# Supply_12V_ISOL.net
KiCad netlist of a schematic drawn in Altium Designer
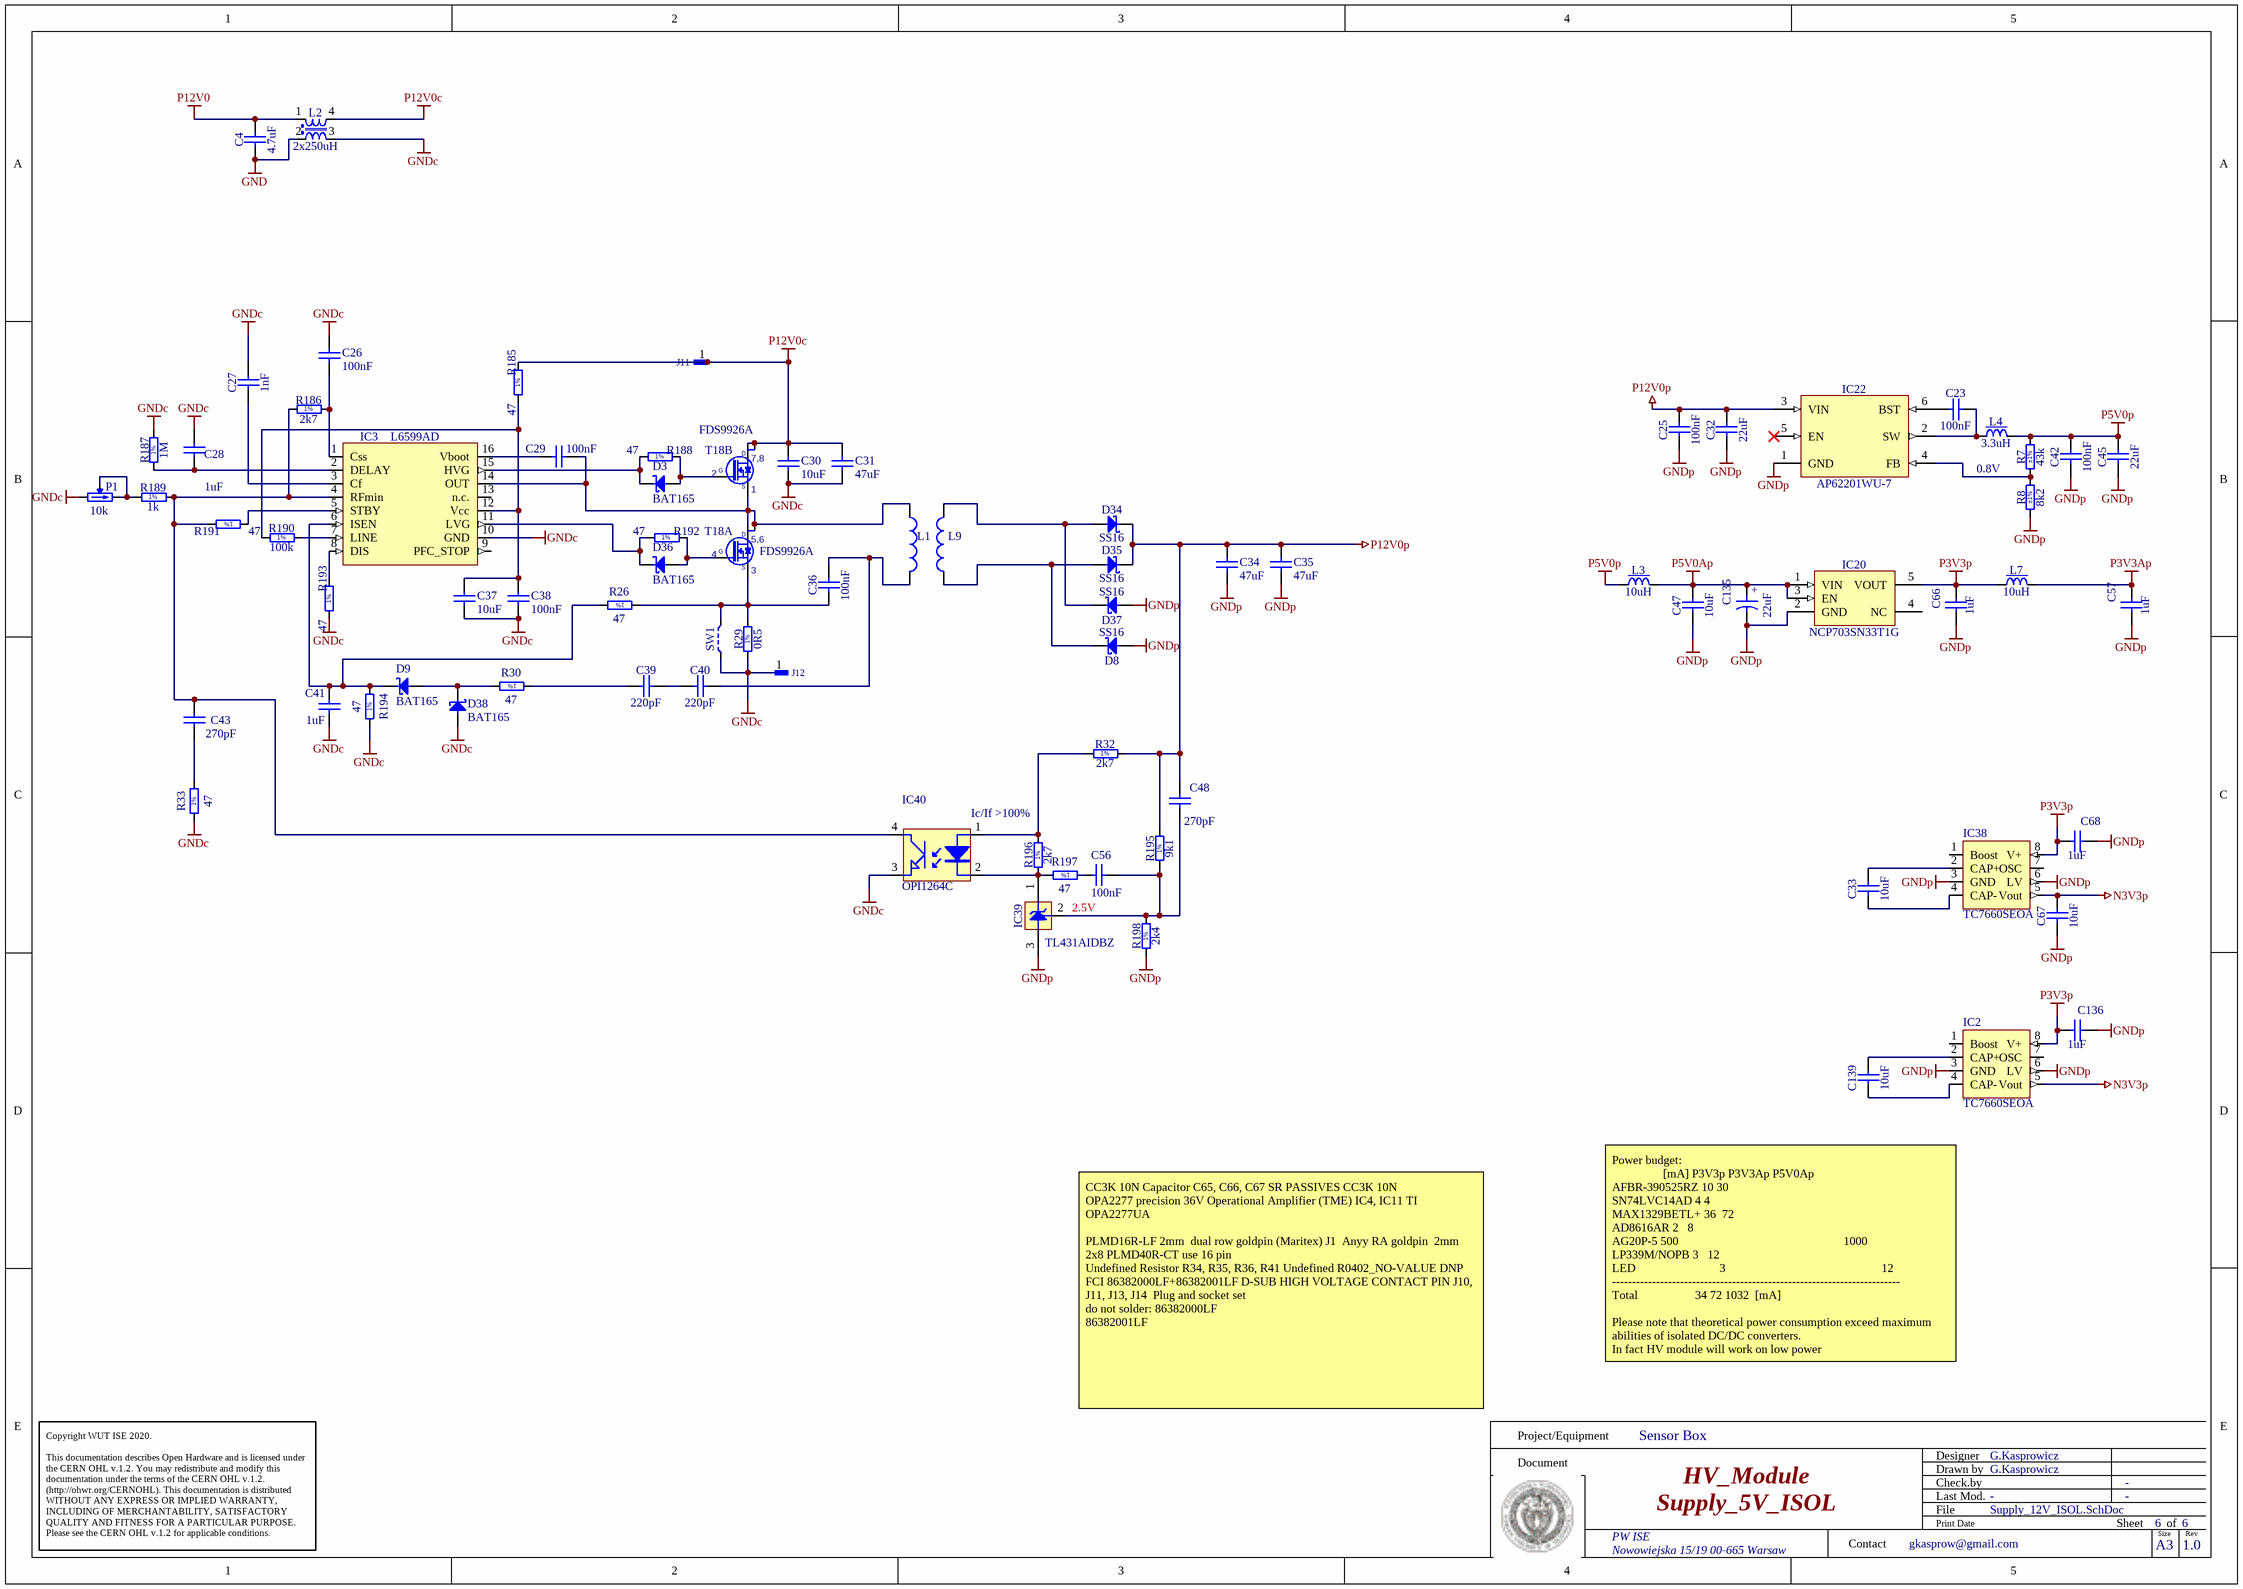
[diagram p0: Supply_12V_ISOL.SchDoc]

(export (version "E")
  (design (tool "Eeschema 10.0.6"))
  (components
    (comp (ref "C4")
      (value "4.7uF")
      (footprint "CAPC2012X145N")
      (description "Non-polarised capacitor")
      (fields
        (field (name "PART NUMBER") "CC0805_4.7UF_50V_10%_X7R")
        (field (name "VOLTAGE") "50V")
        (field (name "AUTHOR") "CERN DEM JMW")
      )
      (libsource (lib "Capacitors") (part "Capacitor - non polarized"))
    )
    (comp (ref "C23")
      (value "100nF")
      (footprint "CAPC1005X55N")
      (description "Non-polarised capacitor")
      (fields
        (field (name "PART NUMBER") "CC0402_100NF_16V_10%_X5R")
        (field (name "VOLTAGE") "16V")
        (field (name "AUTHOR") "CERN DEM JLC")
      )
      (libsource (lib "Capacitors") (part "Capacitor - non polarized"))
    )
    (comp (ref "C25")
      (value "100nF")
      (footprint "CAPC1005X55N")
      (description "Non-polarised capacitor")
      (fields
        (field (name "PART NUMBER") "CC0402_100NF_16V_10%_X5R")
        (field (name "VOLTAGE") "16V")
        (field (name "AUTHOR") "CERN DEM JLC")
      )
      (libsource (lib "Capacitors") (part "Capacitor - non polarized"))
    )
    (comp (ref "C26")
      (value "100nF")
      (footprint "CAPC1005X55N")
      (description "Non-polarised capacitor")
      (fields
        (field (name "PART NUMBER") "CC0402_100NF_16V_10%_X7R")
        (field (name "VOLTAGE") "16V")
        (field (name "AUTHOR") "CERN DEM JLC")
      )
      (libsource (lib "Capacitors") (part "Capacitor - non polarized"))
    )
    (comp (ref "C27")
      (value "1nF")
      (footprint "CAPC1608X90N")
      (description "Non-polarised capacitor")
      (fields
        (field (name "PART NUMBER") "CC0603_1NF_50V_5%_NP0")
        (field (name "VOLTAGE") "50V")
        (field (name "AUTHOR") "CERN DEM JLC")
      )
      (libsource (lib "Capacitors") (part "Capacitor - non polarized"))
    )
    (comp (ref "C28")
      (value "1uF")
      (footprint "CAPC1608X87N")
      (description "Non-polarised capacitor")
      (fields
        (field (name "PART NUMBER") "CC0603_1UF_25V_10%_X7R")
        (field (name "VOLTAGE") "25V")
        (field (name "AUTHOR") "CERN DEM JLC")
      )
      (libsource (lib "Capacitors") (part "Capacitor - non polarized"))
    )
    (comp (ref "C29")
      (value "100nF")
      (footprint "CAPC1005X55N")
      (description "Non-polarised capacitor")
      (fields
        (field (name "PART NUMBER") "CC0402_100NF_16V_10%_X7R")
        (field (name "VOLTAGE") "16V")
        (field (name "AUTHOR") "CERN DEM JLC")
      )
      (libsource (lib "Capacitors") (part "Capacitor - non polarized"))
    )
    (comp (ref "C30")
      (value "10uF")
      (footprint "CAPC3216X180N")
      (description "Non-polarised capacitor")
      (fields
        (field (name "PART NUMBER") "CC1206_10UF_25V_10%_X7R")
        (field (name "VOLTAGE") "25V")
        (field (name "AUTHOR") "CERN DEM JLC")
      )
      (libsource (lib "Capacitors") (part "Capacitor - non polarized"))
    )
    (comp (ref "C31")
      (value "47uF")
      (footprint "CAPC3216X180N")
      (description "Non-polarised capacitor")
      (fields
        (field (name "PART NUMBER") "CC1206_47UF_25V_20%_X5R")
        (field (name "VOLTAGE") "25V")
        (field (name "AUTHOR") "CERN DEM JLC")
      )
      (libsource (lib "Capacitors") (part "Capacitor - non polarized"))
    )
    (comp (ref "C32")
      (value "22uF")
      (footprint "CAPC2012X135N")
      (description "Non-polarised capacitor")
      (fields
        (field (name "PART NUMBER") "CC0805_22UF_16V_10%_X5R")
        (field (name "VOLTAGE") "16V")
        (field (name "AUTHOR") "CERN DEM JLC")
      )
      (libsource (lib "Capacitors") (part "Capacitor - non polarized"))
    )
    (comp (ref "C33")
      (value "10uF")
      (footprint "CAPC1608X80N")
      (description "Non-polarised capacitor")
      (fields
        (field (name "PART NUMBER") "CC0603_10UF_16V_20%_X5R")
        (field (name "VOLTAGE") "16V")
        (field (name "AUTHOR") "CERN DEM MR")
      )
      (libsource (lib "Capacitors") (part "Capacitor - non polarized"))
    )
    (comp (ref "C34")
      (value "47uF")
      (footprint "CAPC3216X180N")
      (description "Non-polarised capacitor")
      (fields
        (field (name "PART NUMBER") "CC1206_47UF_25V_20%_X5R")
        (field (name "VOLTAGE") "25V")
        (field (name "AUTHOR") "CERN DEM JLC")
      )
      (libsource (lib "Capacitors") (part "Capacitor - non polarized"))
    )
    (comp (ref "C35")
      (value "47uF")
      (footprint "CAPC3216X180N")
      (description "Non-polarised capacitor")
      (fields
        (field (name "PART NUMBER") "CC1206_47UF_25V_20%_X5R")
        (field (name "VOLTAGE") "25V")
        (field (name "AUTHOR") "CERN DEM JLC")
      )
      (libsource (lib "Capacitors") (part "Capacitor - non polarized"))
    )
    (comp (ref "C36")
      (value "100nF")
      (footprint "CAPC4532X250N")
      (description "Non-polarised capacitor")
      (fields
        (field (name "PART NUMBER") "CC1812_100NF_500V_10%_X7R")
        (field (name "VOLTAGE") "500V")
        (field (name "AUTHOR") "CERN DEM JMW")
      )
      (libsource (lib "Capacitors") (part "Capacitor - non polarized"))
    )
    (comp (ref "C37")
      (value "10uF")
      (footprint "CAPC3216X180N")
      (description "Non-polarised capacitor")
      (fields
        (field (name "PART NUMBER") "CC1206_10UF_25V_10%_X7R")
        (field (name "VOLTAGE") "25V")
        (field (name "AUTHOR") "CERN DEM JLC")
      )
      (libsource (lib "Capacitors") (part "Capacitor - non polarized"))
    )
    (comp (ref "C38")
      (value "100nF")
      (footprint "CAPC1005X55N")
      (description "Non-polarised capacitor")
      (fields
        (field (name "PART NUMBER") "CC0402_100NF_16V_10%_X7R")
        (field (name "VOLTAGE") "16V")
        (field (name "AUTHOR") "CERN DEM JLC")
      )
      (libsource (lib "Capacitors") (part "Capacitor - non polarized"))
    )
    (comp (ref "C39")
      (value "220pF")
      (footprint "CAPC3225X200N")
      (description "Non-polarised capacitor")
      (fields
        (field (name "PART NUMBER") "CMIC1210_220PF_100V_0.5PF_CORNELL_MC12FA221D-F")
        (field (name "VOLTAGE") "100V")
        (field (name "AUTHOR") "CERN DEM JLC")
      )
      (libsource (lib "Capacitors") (part "Capacitor - non polarized"))
    )
    (comp (ref "C40")
      (value "220pF")
      (footprint "CAPC3225X200N")
      (description "Non-polarised capacitor")
      (fields
        (field (name "PART NUMBER") "CMIC1210_220PF_100V_0.5PF_CORNELL_MC12FA221D-F")
        (field (name "VOLTAGE") "100V")
        (field (name "AUTHOR") "CERN DEM JLC")
      )
      (libsource (lib "Capacitors") (part "Capacitor - non polarized"))
    )
    (comp (ref "C41")
      (value "1uF")
      (footprint "CAPC1608X87N")
      (description "Non-polarised capacitor")
      (fields
        (field (name "PART NUMBER") "CC0603_1UF_25V_10%_X7R")
        (field (name "VOLTAGE") "25V")
        (field (name "AUTHOR") "CERN DEM JLC")
      )
      (libsource (lib "Capacitors") (part "Capacitor - non polarized"))
    )
    (comp (ref "C42")
      (value "100nF")
      (footprint "CAPC1005X55N")
      (description "Non-polarised capacitor")
      (fields
        (field (name "PART NUMBER") "CC0402_100NF_16V_10%_X5R")
        (field (name "VOLTAGE") "16V")
        (field (name "AUTHOR") "CERN DEM JLC")
      )
      (libsource (lib "Capacitors") (part "Capacitor - non polarized"))
    )
    (comp (ref "C43")
      (value "270pF")
      (footprint "CAPC1608X87N")
      (description "Non-polarised capacitor")
      (fields
        (field (name "PART NUMBER") "CC0603_270PF_50V_5%_NP0")
        (field (name "VOLTAGE") "50V")
        (field (name "AUTHOR") "CERN DEM JLC")
      )
      (libsource (lib "Capacitors") (part "Capacitor - non polarized"))
    )
    (comp (ref "C45")
      (value "22uF")
      (footprint "CAPC2012X135N")
      (description "Non-polarised capacitor")
      (fields
        (field (name "PART NUMBER") "CC0805_22UF_16V_10%_X5R")
        (field (name "VOLTAGE") "16V")
        (field (name "AUTHOR") "CERN DEM JLC")
      )
      (libsource (lib "Capacitors") (part "Capacitor - non polarized"))
    )
    (comp (ref "C47")
      (value "10uF")
      (footprint "CAPC1608X80N")
      (description "Non-polarised capacitor")
      (fields
        (field (name "PART NUMBER") "CC0603_10UF_16V_20%_X5R")
        (field (name "VOLTAGE") "16V")
        (field (name "AUTHOR") "CERN DEM MR")
      )
      (libsource (lib "Capacitors") (part "Capacitor - non polarized"))
    )
    (comp (ref "C48")
      (value "270pF")
      (footprint "CAPC1608X87N")
      (description "Non-polarised capacitor")
      (fields
        (field (name "PART NUMBER") "CC0603_270PF_50V_5%_NP0")
        (field (name "VOLTAGE") "50V")
        (field (name "AUTHOR") "CERN DEM JLC")
      )
      (libsource (lib "Capacitors") (part "Capacitor - non polarized"))
    )
    (comp (ref "C56")
      (value "100nF")
      (footprint "CAPC1005X55N")
      (description "Non-polarised capacitor")
      (fields
        (field (name "PART NUMBER") "CC0402_100NF_16V_10%_X7R")
        (field (name "VOLTAGE") "16V")
        (field (name "AUTHOR") "CERN DEM JLC")
      )
      (libsource (lib "Capacitors") (part "Capacitor - non polarized"))
    )
    (comp (ref "C57")
      (value "1uF")
      (footprint "CAPC1005X55N")
      (description "Non-polarised capacitor")
      (fields
        (field (name "PART NUMBER") "CC0402_1UF_16V_10%_X5R")
        (field (name "VOLTAGE") "16V")
        (field (name "AUTHOR") "CERN DEM JLC")
      )
      (libsource (lib "Capacitors") (part "Capacitor - non polarized"))
    )
    (comp (ref "C66")
      (value "1uF")
      (footprint "CAPC1005X55N")
      (description "Non-polarised capacitor")
      (fields
        (field (name "PART NUMBER") "CC0402_1UF_16V_10%_X5R")
        (field (name "VOLTAGE") "16V")
        (field (name "AUTHOR") "CERN DEM JLC")
      )
      (libsource (lib "Capacitors") (part "Capacitor - non polarized"))
    )
    (comp (ref "C67")
      (value "10uF")
      (footprint "CAPC1608X80N")
      (description "Non-polarised capacitor")
      (fields
        (field (name "PART NUMBER") "CC0603_10UF_16V_20%_X5R")
        (field (name "VOLTAGE") "16V")
        (field (name "AUTHOR") "CERN DEM MR")
      )
      (libsource (lib "Capacitors") (part "Capacitor - non polarized"))
    )
    (comp (ref "C68")
      (value "1uF")
      (footprint "CAPC1005X55N")
      (description "Non-polarised capacitor")
      (fields
        (field (name "PART NUMBER") "CC0402_1UF_16V_10%_X5R")
        (field (name "VOLTAGE") "16V")
        (field (name "AUTHOR") "CERN DEM JLC")
      )
      (libsource (lib "Capacitors") (part "Capacitor - non polarized"))
    )
    (comp (ref "C135")
      (value "22uF")
      (footprint "CAPMP3528X210N")
      (description "Polarised capacitor")
      (fields
        (field (name "PART NUMBER") "CTE3528-21_22UF_20V_10%")
        (field (name "VOLTAGE") "20V")
        (field (name "AUTHOR") "CERN DEM JLC")
      )
      (libsource (lib "Capacitors") (part "Capacitor - polarized"))
    )
    (comp (ref "C136")
      (value "1uF")
      (footprint "CAPC1005X55N")
      (description "Non-polarised capacitor")
      (fields
        (field (name "PART NUMBER") "CC0402_1UF_16V_10%_X5R")
        (field (name "VOLTAGE") "16V")
        (field (name "AUTHOR") "CERN DEM JLC")
      )
      (libsource (lib "Capacitors") (part "Capacitor - non polarized"))
    )
    (comp (ref "C139")
      (value "10uF")
      (footprint "CAPC1608X80N")
      (description "Non-polarised capacitor")
      (fields
        (field (name "PART NUMBER") "CC0603_10UF_16V_20%_X5R")
        (field (name "VOLTAGE") "16V")
        (field (name "AUTHOR") "CERN DEM MR")
      )
      (libsource (lib "Capacitors") (part "Capacitor - non polarized"))
    )
    (comp (ref "D3")
      (value "BAT165")
      (footprint "SOD2512X110N")
      (description "Schottky Diode")
      (fields
        (field (name "VOLTAGE") "40V")
        (field (name "POWER") "750mA")
        (field (name "AUTHOR") "CERN DEM JLC")
      )
      (libsource (lib "ICs And Semiconductors") (part "Diode Schottky"))
    )
    (comp (ref "D8")
      (value "SS16")
      (footprint "DIOM5127X229N")
      (description "Schottky Diode")
      (fields
        (field (name "VOLTAGE") "60V")
        (field (name "POWER") "1A")
        (field (name "AUTHOR") "CERN DEM JLC")
      )
      (libsource (lib "ICs And Semiconductors") (part "Diode Schottky"))
    )
    (comp (ref "D9")
      (value "BAT165")
      (footprint "SOD2512X110N")
      (description "Schottky Diode")
      (fields
        (field (name "VOLTAGE") "40V")
        (field (name "POWER") "750mA")
        (field (name "AUTHOR") "CERN DEM JLC")
      )
      (libsource (lib "ICs And Semiconductors") (part "Diode Schottky"))
    )
    (comp (ref "D34")
      (value "SS16")
      (footprint "DIOM5127X229N")
      (description "Schottky Diode")
      (fields
        (field (name "VOLTAGE") "60V")
        (field (name "POWER") "1A")
        (field (name "AUTHOR") "CERN DEM JLC")
      )
      (libsource (lib "ICs And Semiconductors") (part "Diode Schottky"))
    )
    (comp (ref "D35")
      (value "SS16")
      (footprint "DIOM5127X229N")
      (description "Schottky Diode")
      (fields
        (field (name "VOLTAGE") "60V")
        (field (name "POWER") "1A")
        (field (name "AUTHOR") "CERN DEM JLC")
      )
      (libsource (lib "ICs And Semiconductors") (part "Diode Schottky"))
    )
    (comp (ref "D36")
      (value "BAT165")
      (footprint "SOD2512X110N")
      (description "Schottky Diode")
      (fields
        (field (name "VOLTAGE") "40V")
        (field (name "POWER") "750mA")
        (field (name "AUTHOR") "CERN DEM JLC")
      )
      (libsource (lib "ICs And Semiconductors") (part "Diode Schottky"))
    )
    (comp (ref "D37")
      (value "SS16")
      (footprint "DIOM5127X229N")
      (description "Schottky Diode")
      (fields
        (field (name "VOLTAGE") "60V")
        (field (name "POWER") "1A")
        (field (name "AUTHOR") "CERN DEM JLC")
      )
      (libsource (lib "ICs And Semiconductors") (part "Diode Schottky"))
    )
    (comp (ref "D38")
      (value "BAT165")
      (footprint "SOD2512X110N")
      (description "Schottky Diode")
      (fields
        (field (name "VOLTAGE") "40V")
        (field (name "POWER") "750mA")
        (field (name "AUTHOR") "CERN DEM JLC")
      )
      (libsource (lib "ICs And Semiconductors") (part "Diode Schottky"))
    )
    (comp (ref "IC2")
      (value "TC7660SEOA")
      (footprint "SO-8")
      (description "20mA PUMP DC-TO-DC VOLTAGE CONVERTER")
      (libsource (lib "LIBRARY_SCH") (part "PM_TC7660"))
    )
    (comp (ref "IC3")
      (value "L6599AD")
      (footprint "SOIC127P600X175-16N")
      (description "Improved high voltage resonant LLC controller")
      (fields (field (name "MANUFACTURER") "ST MICROELECTRONICS") (field (name "AUTHOR") "GK"))
      (libsource (lib "LIBRARY_SCH") (part "PM_L6599"))
    )
    (comp (ref "IC20")
      (value "NCP703SN33T1G")
      (footprint "SOT95P275X110-5N")
      (description "3.3V 300mA, Ultra-Low Quiescent Current, IQ 12uA, Ultra-Low Noise, LDO Voltage Regulator")
      (fields (field (name "MANUFACTURER") "ON SEMICONDUCTOR") (field (name "AUTHOR") "CERN DEM JLC"))
      (libsource (lib "ICs And Semiconductors") (part "NCP703SN"))
    )
    (comp (ref "IC22")
      (value "AP62201WU-7")
      (footprint "SOT95P280X100-6N")
      (description "4.2V TO 18V INPUT, 2A LOW IQ SYNCHRONOUS BUCK CONVERTER")
      (fields (field (name "MANUFACTURER") "DIODES INCORPORATED") (field (name "AUTHOR") "CERN DEM HF"))
      (libsource (lib "ICs And Semiconductors") (part "AP62201WU"))
    )
    (comp (ref "IC38")
      (value "TC7660SEOA")
      (footprint "SO-8")
      (description "20mA PUMP DC-TO-DC VOLTAGE CONVERTER")
      (libsource (lib "LIBRARY_SCH") (part "PM_TC7660"))
    )
    (comp (ref "IC39")
      (value "TL431AIDBZ")
      (footprint "SOT95P237X112-3N")
      (description "Precision Reference 1=Cathode 2=Adj 3=Anode")
      (fields (field (name "MANUFACTURER") "TEXAS INSTRUMENTS") (field (name "AUTHOR") "CERN DEM JMW"))
      (libsource (lib "ICs And Semiconductors") (part "VREF 1C-2ADJ-3A"))
    )
    (comp (ref "IC40")
      (value "OPI1264C")
      (footprint "OPI1264C")
      (description "10kV opto-coupler")
      (libsource (lib "LIBRARY_SCH") (part "OPTO-OPI1264C"))
    )
    (comp (ref "J11")
      (value "SMD Pad")
      (footprint "R400X300")
      (description "Single SMD Pad")
      (fields (field (name "PART NUMBER") "SMD_PAD_4X3MM") (field (name "AUTHOR") "CERN DEM JLC"))
      (libsource (lib "Eletro-mechanical") (part "Single SMD Pad"))
    )
    (comp (ref "J12")
      (value "SMD Pad")
      (footprint "R400X300")
      (description "Single SMD Pad")
      (fields (field (name "PART NUMBER") "SMD_PAD_4X3MM") (field (name "AUTHOR") "CERN DEM JLC"))
      (libsource (lib "") (part "Single SMD Pad_1"))
    )
    (comp (ref "L1")
      (value "6.8uH")
      (footprint "760308101104")
      (description "WE-WPCC Wireless Power Transfer Transmitter Coil, THT, works with Qi Tx IC's, 6.8uH, 50W")
      (fields
        (field (name "MANUFACTURER PART NUMBER") "760308101104")
        (field (name "MANUFACTURER") "Wurth Elektronik")
      )
      (libsource (lib "Altium_WE-WPCC (rev23b)") (part "760308101104"))
    )
    (comp (ref "L2")
      (value "2x250uH")
      (footprint "IND_WURTH_WE-SL2")
      (description "Inductor Common Mode")
      (fields
        (field (name "PART NUMBER") "IND_250UH_50%_WURTH_WE-SL2-744224")
        (field (name "POWER") "1.2A")
        (field (name "AUTHOR") "CERN DEM JLC")
      )
      (libsource (lib "Inductors & Transformers") (part "Inductor Common Mode 1Dot-4 2Dot-3"))
    )
    (comp (ref "L3")
      (value "10uH")
      (footprint "IND_BOURNS_PM43")
      (description "Inductor With Core")
      (fields
        (field (name "PART NUMBER") "IND_10UH_20%_BOURNS_PM43")
        (field (name "POWER") "1.15A")
        (field (name "AUTHOR") "CERN DEM JLC")
      )
      (libsource (lib "Inductors & Transformers") (part "Inductor With Magnetic core"))
    )
    (comp (ref "L4")
      (value "3.3uH")
      (footprint "IND_WURTH_WE-TPC_4828")
      (description "Inductor With Core")
      (fields
        (field (name "PART NUMBER") "IND_3.3UH_30%_WURTH_WE-TPC_744043003")
        (field (name "POWER") "2.15A")
        (field (name "AUTHOR") "CERN DEM JLC")
      )
      (libsource (lib "Inductors & Transformers") (part "Inductor With Magnetic core"))
    )
    (comp (ref "L7")
      (value "10uH")
      (footprint "IND_BOURNS_PM43")
      (description "Inductor With Core")
      (fields
        (field (name "PART NUMBER") "IND_10UH_20%_BOURNS_PM43")
        (field (name "POWER") "1.15A")
        (field (name "AUTHOR") "CERN DEM JLC")
      )
      (libsource (lib "Inductors & Transformers") (part "Inductor With Magnetic core"))
    )
    (comp (ref "L9")
      (value "6.8uH")
      (footprint "760308101104")
      (description "WE-WPCC Wireless Power Transfer Transmitter Coil, THT, works with Qi Tx IC's, 6.8uH, 50W")
      (fields
        (field (name "MANUFACTURER PART NUMBER") "760308101104")
        (field (name "MANUFACTURER") "Wurth Elektronik")
      )
      (libsource (lib "Altium_WE-WPCC (rev23b)") (part "760308101104"))
    )
    (comp (ref "P1")
      (value "10k")
      (footprint "TRIM_BOURNS_3314G-1")
      (description "Trimming Potentiometer")
      (fields
        (field (name "PART NUMBER") "TRIM_1T_10K_BOURNS_3314G-1-103E")
        (field (name "POWER") "0.25W")
        (field (name "AUTHOR") "CERN DEM JLC")
      )
      (libsource (lib "Resistors") (part "Trimming Potentiometer"))
    )
    (comp (ref "R7")
      (value "43k")
      (footprint "RESC1005X40N")
      (description "Resistor - 1%")
      (fields
        (field (name "TOLERANCE") "±1%")
        (field (name "PART NUMBER") "R0402_43K_1%_0.0625W_100PPM")
        (field (name "POWER") "0.0625W")
        (field (name "AUTHOR") "CERN DEM JLC")
      )
      (libsource (lib "") (part "Resistor - 1%_1"))
    )
    (comp (ref "R8")
      (value "8k2")
      (footprint "RESC1005X40N")
      (description "Resistor - 1%")
      (fields
        (field (name "TOLERANCE") "±1%")
        (field (name "PART NUMBER") "R0402_8K2_1%_0.0625W_100PPM")
        (field (name "POWER") "0.0625W")
        (field (name "AUTHOR") "CERN DEM JLC")
      )
      (libsource (lib "") (part "Resistor - 1%_1"))
    )
    (comp (ref "R26")
      (value "47")
      (footprint "RESC1608X55N")
      (description "Resistor - 1%")
      (fields
        (field (name "PART NUMBER") "R0603_47R_1%_0.1W_100PPM")
        (field (name "POWER") "0.1W")
        (field (name "AUTHOR") "CERN DEM JLC")
      )
      (libsource (lib "Resistors") (part "Resistor - 1%"))
    )
    (comp (ref "R29")
      (value "0R5")
      (footprint "RESC6532X80N")
      (description "Resistor - 1%")
      (fields
        (field (name "PART NUMBER") "R2512_0R5_1%_1.5W_100PPM")
        (field (name "POWER") "1.5W")
        (field (name "AUTHOR") "CERN DEM JLC")
      )
      (libsource (lib "Resistors") (part "Resistor - 1%"))
    )
    (comp (ref "R30")
      (value "47")
      (footprint "RESC1608X55N")
      (description "Resistor - 1%")
      (fields
        (field (name "PART NUMBER") "R0603_47R_1%_0.1W_100PPM")
        (field (name "POWER") "0.1W")
        (field (name "AUTHOR") "CERN DEM JLC")
      )
      (libsource (lib "Resistors") (part "Resistor - 1%"))
    )
    (comp (ref "R32")
      (value "2k7")
      (footprint "RESC1608X55N")
      (description "Resistor - 1%")
      (fields
        (field (name "PART NUMBER") "R0603_2K7_1%_0.1W_100PPM")
        (field (name "POWER") "0.1W")
        (field (name "AUTHOR") "CERN DEM JLC")
      )
      (libsource (lib "Resistors") (part "Resistor - 1%"))
    )
    (comp (ref "R33")
      (value "47")
      (footprint "RESC1608X55N")
      (description "Resistor - 1%")
      (fields
        (field (name "PART NUMBER") "R0603_47R_1%_0.1W_100PPM")
        (field (name "POWER") "0.1W")
        (field (name "AUTHOR") "CERN DEM JLC")
      )
      (libsource (lib "Resistors") (part "Resistor - 1%"))
    )
    (comp (ref "R185")
      (value "47")
      (footprint "RESC1608X55N")
      (description "Resistor - 1%")
      (fields
        (field (name "PART NUMBER") "R0603_47R_1%_0.1W_100PPM")
        (field (name "POWER") "0.1W")
        (field (name "AUTHOR") "CERN DEM JLC")
      )
      (libsource (lib "Resistors") (part "Resistor - 1%"))
    )
    (comp (ref "R186")
      (value "2k7")
      (footprint "RESC1608X55N")
      (description "Resistor - 1%")
      (fields
        (field (name "PART NUMBER") "R0603_2K7_1%_0.1W_100PPM")
        (field (name "POWER") "0.1W")
        (field (name "AUTHOR") "CERN DEM JLC")
      )
      (libsource (lib "Resistors") (part "Resistor - 1%"))
    )
    (comp (ref "R187")
      (value "1M")
      (footprint "RESC1608X55N")
      (description "Resistor - 1%")
      (fields
        (field (name "PART NUMBER") "R0603_1M_1%_0.1W_100PPM")
        (field (name "POWER") "0.1W")
        (field (name "AUTHOR") "CERN DEM JLC")
      )
      (libsource (lib "Resistors") (part "Resistor - 1%"))
    )
    (comp (ref "R188")
      (value "47")
      (footprint "RESC1608X55N")
      (description "Resistor - 1%")
      (fields
        (field (name "PART NUMBER") "R0603_47R_1%_0.1W_100PPM")
        (field (name "POWER") "0.1W")
        (field (name "AUTHOR") "CERN DEM JLC")
      )
      (libsource (lib "Resistors") (part "Resistor - 1%"))
    )
    (comp (ref "R189")
      (value "1k")
      (footprint "RESC1005X40N")
      (description "Resistor - 1%")
      (fields
        (field (name "PART NUMBER") "R0402_1K_1%_0.0625W_100PPM")
        (field (name "POWER") "0.0625W")
        (field (name "AUTHOR") "CERN DEM JLC")
      )
      (libsource (lib "Resistors") (part "Resistor - 1%"))
    )
    (comp (ref "R190")
      (value "100k")
      (footprint "RESC1005X40N")
      (description "Resistor - 1%")
      (fields
        (field (name "PART NUMBER") "R0402_100K_1%_0.0625W_100PPM")
        (field (name "POWER") "0.0625W")
        (field (name "AUTHOR") "CERN DEM JLC")
      )
      (libsource (lib "Resistors") (part "Resistor - 1%"))
    )
    (comp (ref "R191")
      (value "47")
      (footprint "RESC1608X55N")
      (description "Resistor - 1%")
      (fields
        (field (name "PART NUMBER") "R0603_47R_1%_0.1W_100PPM")
        (field (name "POWER") "0.1W")
        (field (name "AUTHOR") "CERN DEM JLC")
      )
      (libsource (lib "Resistors") (part "Resistor - 1%"))
    )
    (comp (ref "R192")
      (value "47")
      (footprint "RESC1608X55N")
      (description "Resistor - 1%")
      (fields
        (field (name "PART NUMBER") "R0603_47R_1%_0.1W_100PPM")
        (field (name "POWER") "0.1W")
        (field (name "AUTHOR") "CERN DEM JLC")
      )
      (libsource (lib "Resistors") (part "Resistor - 1%"))
    )
    (comp (ref "R193")
      (value "47")
      (footprint "RESC1608X55N")
      (description "Resistor - 1%")
      (fields
        (field (name "PART NUMBER") "R0603_47R_1%_0.1W_100PPM")
        (field (name "POWER") "0.1W")
        (field (name "AUTHOR") "CERN DEM JLC")
      )
      (libsource (lib "Resistors") (part "Resistor - 1%"))
    )
    (comp (ref "R194")
      (value "47")
      (footprint "RESC1608X55N")
      (description "Resistor - 1%")
      (fields
        (field (name "PART NUMBER") "R0603_47R_1%_0.1W_100PPM")
        (field (name "POWER") "0.1W")
        (field (name "AUTHOR") "CERN DEM JLC")
      )
      (libsource (lib "Resistors") (part "Resistor - 1%"))
    )
    (comp (ref "R195")
      (value "9k1")
      (footprint "RESC1608X55N")
      (description "Resistor - 1%")
      (fields
        (field (name "PART NUMBER") "R0603_9K1_1%_0.1W_100PPM")
        (field (name "POWER") "0.1W")
        (field (name "AUTHOR") "CERN DEM JLC")
      )
      (libsource (lib "Resistors") (part "Resistor - 1%"))
    )
    (comp (ref "R196")
      (value "2k7")
      (footprint "RESC1608X55N")
      (description "Resistor - 1%")
      (fields
        (field (name "PART NUMBER") "R0603_2K7_1%_0.1W_100PPM")
        (field (name "POWER") "0.1W")
        (field (name "AUTHOR") "CERN DEM JLC")
      )
      (libsource (lib "Resistors") (part "Resistor - 1%"))
    )
    (comp (ref "R197")
      (value "47")
      (footprint "RESC1608X55N")
      (description "Resistor - 1%")
      (fields
        (field (name "PART NUMBER") "R0603_47R_1%_0.1W_100PPM")
        (field (name "POWER") "0.1W")
        (field (name "AUTHOR") "CERN DEM JLC")
      )
      (libsource (lib "Resistors") (part "Resistor - 1%"))
    )
    (comp (ref "R198")
      (value "2k4")
      (footprint "RESC1608X55N")
      (description "Resistor - 1%")
      (fields
        (field (name "PART NUMBER") "R0603_2K4_1%_0.1W_100PPM")
        (field (name "POWER") "0.1W")
        (field (name "AUTHOR") "CERN DEM JLC")
      )
      (libsource (lib "Resistors") (part "Resistor - 1%"))
    )
    (comp (ref "SW1")
      (value "Switch")
      (footprint "JUMPSMD0805_G50")
      (description "2 SMD Pads for Bound by Solder  Drop")
      (fields
        (field (name "PART NUMBER") "JUMPSMD0805_G50")
        (field (name "MANUFACTURER") "None")
        (field (name "AUTHOR") "CERN DEM JLC")
      )
      (libsource (lib "Eletro-mechanical") (part "SMD Solder Jumper"))
    )
    (comp (ref "T18")
      (value "FDS9926A")
      (footprint "SOIC127P600X175-8N")
      (description "20V DUAL N-Channel 2.5V Specified PowerTrench MOSFET")
      (fields (field (name "MANUFACTURER") "FAIRCHILD SEMICONDUCTOR") (field (name "AUTHOR") "CERN DEM BC"))
      (libsource (lib "ICs And Semiconductors") (part "FDS9926A"))
    )
  )
  (nets
    (net (code "1") (name "GND") (class "Default")
      (node (ref "C4") (pin "1") (pinfunction "1_1") (pintype "passive"))
      (node (ref "L2") (pin "2") (pinfunction "2_2") (pintype "passive"))
    )
    (net (code "2") (name "GNDc") (class "Default")
      (node (ref "C26") (pin "1") (pinfunction "1_1") (pintype "passive"))
      (node (ref "C27") (pin "2") (pinfunction "2_2") (pintype "passive"))
      (node (ref "C28") (pin "2") (pinfunction "2_2") (pintype "passive"))
      (node (ref "C30") (pin "2") (pinfunction "2_2") (pintype "passive"))
      (node (ref "C31") (pin "2") (pinfunction "2_2") (pintype "passive"))
      (node (ref "C37") (pin "2") (pinfunction "2_2") (pintype "passive"))
      (node (ref "C38") (pin "2") (pinfunction "2_2") (pintype "passive"))
      (node (ref "C41") (pin "1") (pinfunction "1_1") (pintype "passive"))
      (node (ref "D38") (pin "2") (pinfunction "A_2") (pintype "passive"))
      (node (ref "IC3") (pin "10") (pinfunction "GND_10") (pintype "power_in"))
      (node (ref "IC40") (pin "3") (pinfunction "E_3") (pintype "passive"))
      (node (ref "J12") (pin "1") (pinfunction "1_1") (pintype "bidirectional"))
      (node (ref "L2") (pin "3") (pinfunction "3_3") (pintype "passive"))
      (node (ref "P1") (pin "1") (pinfunction "CCW_1") (pintype "passive"))
      (node (ref "R187") (pin "2") (pinfunction "2_2") (pintype "passive"))
      (node (ref "R193") (pin "1") (pinfunction "1_1") (pintype "passive"))
      (node (ref "R194") (pin "1") (pinfunction "1_1") (pintype "passive"))
      (node (ref "R29") (pin "1") (pinfunction "1_1") (pintype "passive"))
      (node (ref "R33") (pin "1") (pinfunction "1_1") (pintype "passive"))
      (node (ref "SW1") (pin "1") (pinfunction "1_1") (pintype "passive"))
    )
    (net (code "3") (name "GNDp") (class "Default")
      (node (ref "C135") (pin "2") (pinfunction "2_2") (pintype "passive"))
      (node (ref "C136") (pin "2") (pinfunction "2_2") (pintype "passive"))
      (node (ref "C25") (pin "1") (pinfunction "1_1") (pintype "passive"))
      (node (ref "C32") (pin "1") (pinfunction "1_1") (pintype "passive"))
      (node (ref "C34") (pin "2") (pinfunction "2_2") (pintype "passive"))
      (node (ref "C35") (pin "2") (pinfunction "2_2") (pintype "passive"))
      (node (ref "C42") (pin "1") (pinfunction "1_1") (pintype "passive"))
      (node (ref "C45") (pin "1") (pinfunction "1_1") (pintype "passive"))
      (node (ref "C47") (pin "1") (pinfunction "1_1") (pintype "passive"))
      (node (ref "C57") (pin "1") (pinfunction "1_1") (pintype "passive"))
      (node (ref "C66") (pin "1") (pinfunction "1_1") (pintype "passive"))
      (node (ref "C67") (pin "1") (pinfunction "1_1") (pintype "passive"))
      (node (ref "C68") (pin "2") (pinfunction "2_2") (pintype "passive"))
      (node (ref "D37") (pin "2") (pinfunction "A_2") (pintype "passive"))
      (node (ref "D8") (pin "2") (pinfunction "A_2") (pintype "passive"))
      (node (ref "IC2") (pin "3") (pinfunction "GND_3") (pintype "power_in"))
      (node (ref "IC2") (pin "6") (pinfunction "LV_6") (pintype "output"))
      (node (ref "IC20") (pin "2") (pinfunction "GND_2") (pintype "power_in"))
      (node (ref "IC22") (pin "1") (pinfunction "GND_1") (pintype "power_in"))
      (node (ref "IC38") (pin "3") (pinfunction "GND_3") (pintype "power_in"))
      (node (ref "IC38") (pin "6") (pinfunction "LV_6") (pintype "output"))
      (node (ref "IC39") (pin "3") (pinfunction "A_3") (pintype "passive"))
      (node (ref "R198") (pin "1") (pinfunction "1_1") (pintype "passive"))
      (node (ref "R8") (pin "1") (pinfunction "1_1") (pintype "passive"))
    )
    (net (code "4") (name "N3V3p") (class "Default")
      (node (ref "C67") (pin "2") (pinfunction "2_2") (pintype "passive"))
      (node (ref "IC2") (pin "5") (pinfunction "Vout_5") (pintype "output"))
      (node (ref "IC38") (pin "5") (pinfunction "Vout_5") (pintype "output"))
    )
    (net (code "5") (name "Net-(C36-Pad2)") (class "Default")
      (node (ref "C36") (pin "2") (pinfunction "2_2") (pintype "passive"))
      (node (ref "C40") (pin "2") (pinfunction "2_2") (pintype "passive"))
      (node (ref "L1") (pin "2") (pinfunction "2_2") (pintype "passive"))
    )
    (net (code "6") (name "Net-(C39-Pad1)") (class "Default")
      (node (ref "C39") (pin "1") (pinfunction "1_1") (pintype "passive"))
      (node (ref "R30") (pin "1") (pinfunction "1_1") (pintype "passive"))
    )
    (net (code "7") (name "Net-(C39-Pad2)") (class "Default")
      (node (ref "C39") (pin "2") (pinfunction "2_2") (pintype "passive"))
      (node (ref "C40") (pin "1") (pinfunction "1_1") (pintype "passive"))
    )
    (net (code "8") (name "Net-(C43-Pad1)") (class "Default")
      (node (ref "C43") (pin "1") (pinfunction "1_1") (pintype "passive"))
      (node (ref "R33") (pin "2") (pinfunction "2_2") (pintype "passive"))
    )
    (net (code "9") (name "Net-(C56-Pad2)") (class "Default")
      (node (ref "C56") (pin "2") (pinfunction "2_2") (pintype "passive"))
      (node (ref "R197") (pin "1") (pinfunction "1_1") (pintype "passive"))
    )
    (net (code "10") (name "Net-(D3-A)") (class "Default")
      (node (ref "D3") (pin "2") (pinfunction "A_2") (pintype "passive"))
      (node (ref "R188") (pin "2") (pinfunction "2_2") (pintype "passive"))
      (node (ref "T18") (pin "2") (pinfunction "G_2") (pintype "passive"))
    )
    (net (code "11") (name "Net-(D3-C)") (class "Default")
      (node (ref "D3") (pin "1") (pinfunction "C_1") (pintype "passive"))
      (node (ref "IC3") (pin "15") (pinfunction "HVG_15") (pintype "output"))
      (node (ref "R188") (pin "1") (pinfunction "1_1") (pintype "passive"))
    )
    (net (code "12") (name "Net-(D9-C)") (class "Default")
      (node (ref "C41") (pin "2") (pinfunction "2_2") (pintype "passive"))
      (node (ref "D9") (pin "1") (pinfunction "C_1") (pintype "passive"))
      (node (ref "IC3") (pin "6") (pinfunction "ISEN_6") (pintype "input"))
      (node (ref "R194") (pin "2") (pinfunction "2_2") (pintype "passive"))
      (node (ref "R26") (pin "2") (pinfunction "2_2") (pintype "passive"))
    )
    (net (code "13") (name "Net-(D34-A)") (class "Default")
      (node (ref "D34") (pin "2") (pinfunction "A_2") (pintype "passive"))
      (node (ref "D37") (pin "1") (pinfunction "C_1") (pintype "passive"))
      (node (ref "L9") (pin "2") (pinfunction "2_2") (pintype "passive"))
    )
    (net (code "14") (name "Net-(D35-A)") (class "Default")
      (node (ref "D35") (pin "2") (pinfunction "A_2") (pintype "passive"))
      (node (ref "D8") (pin "1") (pinfunction "C_1") (pintype "passive"))
      (node (ref "L9") (pin "1") (pinfunction "1_1") (pintype "passive"))
    )
    (net (code "15") (name "Net-(D36-A)") (class "Default")
      (node (ref "D36") (pin "2") (pinfunction "A_2") (pintype "passive"))
      (node (ref "R192") (pin "2") (pinfunction "2_2") (pintype "passive"))
      (node (ref "T18") (pin "4") (pinfunction "G_4") (pintype "passive"))
    )
    (net (code "16") (name "Net-(D36-C)") (class "Default")
      (node (ref "D36") (pin "1") (pinfunction "C_1") (pintype "passive"))
      (node (ref "IC3") (pin "11") (pinfunction "LVG_11") (pintype "output"))
      (node (ref "R192") (pin "1") (pinfunction "1_1") (pintype "passive"))
    )
    (net (code "17") (name "Net-(D38-C)") (class "Default")
      (node (ref "D38") (pin "1") (pinfunction "C_1") (pintype "passive"))
      (node (ref "D9") (pin "2") (pinfunction "A_2") (pintype "passive"))
      (node (ref "R30") (pin "2") (pinfunction "2_2") (pintype "passive"))
    )
    (net (code "18") (name "Net-(IC2-CAP+)") (class "Default")
      (node (ref "C139") (pin "2") (pinfunction "2_2") (pintype "passive"))
      (node (ref "IC2") (pin "2") (pinfunction "CAP+_2") (pintype "passive"))
    )
    (net (code "19") (name "Net-(IC2-CAP-)") (class "Default")
      (node (ref "C139") (pin "1") (pinfunction "1_1") (pintype "passive"))
      (node (ref "IC2") (pin "4") (pinfunction "CAP-_4") (pintype "power_in"))
    )
    (net (code "20") (name "Net-(IC3-Cf)") (class "Default")
      (node (ref "C27") (pin "1") (pinfunction "1_1") (pintype "passive"))
      (node (ref "IC3") (pin "3") (pinfunction "Cf_3") (pintype "passive"))
    )
    (net (code "21") (name "Net-(IC3-Css)") (class "Default")
      (node (ref "C26") (pin "2") (pinfunction "2_2") (pintype "passive"))
      (node (ref "IC3") (pin "1") (pinfunction "Css_1") (pintype "passive"))
      (node (ref "R186") (pin "2") (pinfunction "2_2") (pintype "passive"))
    )
    (net (code "22") (name "Net-(IC3-DELAY)") (class "Default")
      (node (ref "C28") (pin "1") (pinfunction "1_1") (pintype "passive"))
      (node (ref "IC3") (pin "2") (pinfunction "DELAY_2") (pintype "passive"))
      (node (ref "R187") (pin "1") (pinfunction "1_1") (pintype "passive"))
    )
    (net (code "23") (name "Net-(IC3-DIS)") (class "Default")
      (node (ref "IC3") (pin "8") (pinfunction "DIS_8") (pintype "input"))
      (node (ref "R193") (pin "2") (pinfunction "2_2") (pintype "passive"))
    )
    (net (code "24") (name "Net-(IC3-LINE)") (class "Default")
      (node (ref "IC3") (pin "7") (pinfunction "LINE_7") (pintype "input"))
      (node (ref "R190") (pin "2") (pinfunction "2_2") (pintype "passive"))
    )
    (net (code "25") (name "Net-(IC3-OUT)") (class "Default")
      (node (ref "C29") (pin "2") (pinfunction "2_2") (pintype "passive"))
      (node (ref "IC3") (pin "14") (pinfunction "OUT_14") (pintype "passive"))
      (node (ref "L1") (pin "1") (pinfunction "1_1") (pintype "passive"))
      (node (ref "T18") (pin "1") (pinfunction "S_1") (pintype "passive"))
      (node (ref "T18") (pin "5") (pinfunction "D_5") (pintype "passive"))
      (node (ref "T18") (pin "6") (pinfunction "D_6") (pintype "passive"))
    )
    (net (code "26") (name "Net-(IC3-RFmin)") (class "Default")
      (node (ref "C43") (pin "2") (pinfunction "2_2") (pintype "passive"))
      (node (ref "IC3") (pin "4") (pinfunction "RFmin_4") (pintype "passive"))
      (node (ref "IC40") (pin "4") (pinfunction "C_4") (pintype "passive"))
      (node (ref "R186") (pin "1") (pinfunction "1_1") (pintype "passive"))
      (node (ref "R189") (pin "2") (pinfunction "2_2") (pintype "passive"))
      (node (ref "R191") (pin "2") (pinfunction "2_2") (pintype "passive"))
    )
    (net (code "27") (name "Net-(IC3-STBY)") (class "Default")
      (node (ref "IC3") (pin "5") (pinfunction "STBY_5") (pintype "input"))
      (node (ref "R191") (pin "1") (pinfunction "1_1") (pintype "passive"))
    )
    (net (code "28") (name "Net-(IC3-Vboot)") (class "Default")
      (node (ref "C29") (pin "1") (pinfunction "1_1") (pintype "passive"))
      (node (ref "IC3") (pin "16") (pinfunction "Vboot_16") (pintype "power_in"))
    )
    (net (code "29") (name "Net-(IC3-Vcc)") (class "Default")
      (node (ref "C37") (pin "1") (pinfunction "1_1") (pintype "passive"))
      (node (ref "C38") (pin "1") (pinfunction "1_1") (pintype "passive"))
      (node (ref "IC3") (pin "12") (pinfunction "Vcc_12") (pintype "power_in"))
      (node (ref "R185") (pin "1") (pinfunction "1_1") (pintype "passive"))
      (node (ref "R190") (pin "1") (pinfunction "1_1") (pintype "passive"))
    )
    (net (code "30") (name "Net-(IC22-BST)") (class "Default")
      (node (ref "C23") (pin "1") (pinfunction "1_1") (pintype "passive"))
      (node (ref "IC22") (pin "6") (pinfunction "BST_6") (pintype "input"))
    )
    (net (code "31") (name "Net-(IC22-FB)") (class "Default")
      (node (ref "IC22") (pin "4") (pinfunction "FB_4") (pintype "input"))
      (node (ref "R7") (pin "1") (pinfunction "1_1") (pintype "passive"))
      (node (ref "R8") (pin "2") (pinfunction "2_2") (pintype "passive"))
    )
    (net (code "32") (name "Net-(IC22-SW)") (class "Default")
      (node (ref "C23") (pin "2") (pinfunction "2_2") (pintype "passive"))
      (node (ref "IC22") (pin "2") (pinfunction "SW_2") (pintype "output"))
      (node (ref "L4") (pin "1") (pinfunction "1_1") (pintype "passive"))
    )
    (net (code "33") (name "Net-(IC38-CAP+)") (class "Default")
      (node (ref "C33") (pin "2") (pinfunction "2_2") (pintype "passive"))
      (node (ref "IC38") (pin "2") (pinfunction "CAP+_2") (pintype "passive"))
    )
    (net (code "34") (name "Net-(IC38-CAP-)") (class "Default")
      (node (ref "C33") (pin "1") (pinfunction "1_1") (pintype "passive"))
      (node (ref "IC38") (pin "4") (pinfunction "CAP-_4") (pintype "power_in"))
    )
    (net (code "35") (name "Net-(IC39-Adj)") (class "Default")
      (node (ref "C48") (pin "1") (pinfunction "1_1") (pintype "passive"))
      (node (ref "C56") (pin "1") (pinfunction "1_1") (pintype "passive"))
      (node (ref "IC39") (pin "2") (pinfunction "Adj_2") (pintype "passive"))
      (node (ref "R195") (pin "1") (pinfunction "1_1") (pintype "passive"))
      (node (ref "R198") (pin "2") (pinfunction "2_2") (pintype "passive"))
    )
    (net (code "36") (name "Net-(IC39-C)") (class "Default")
      (node (ref "IC39") (pin "1") (pinfunction "C_1") (pintype "passive"))
      (node (ref "IC40") (pin "2") (pinfunction "K_2") (pintype "passive"))
      (node (ref "R196") (pin "1") (pinfunction "1_1") (pintype "passive"))
      (node (ref "R197") (pin "2") (pinfunction "2_2") (pintype "passive"))
    )
    (net (code "37") (name "Net-(IC40-A)") (class "Default")
      (node (ref "IC40") (pin "1") (pinfunction "A_1") (pintype "passive"))
      (node (ref "R196") (pin "2") (pinfunction "2_2") (pintype "passive"))
      (node (ref "R32") (pin "1") (pinfunction "1_1") (pintype "passive"))
    )
    (net (code "38") (name "Net-(P1-CW)") (class "Default")
      (node (ref "P1") (pin "2") (pinfunction "W_2") (pintype "passive"))
      (node (ref "P1") (pin "3") (pinfunction "CW_3") (pintype "passive"))
      (node (ref "R189") (pin "1") (pinfunction "1_1") (pintype "passive"))
    )
    (net (code "39") (name "Net-(T18A-S)") (class "Default")
      (node (ref "C36") (pin "1") (pinfunction "1_1") (pintype "passive"))
      (node (ref "R26") (pin "1") (pinfunction "1_1") (pintype "passive"))
      (node (ref "R29") (pin "2") (pinfunction "2_2") (pintype "passive"))
      (node (ref "SW1") (pin "2") (pinfunction "2_2") (pintype "passive"))
      (node (ref "T18") (pin "3") (pinfunction "S_3") (pintype "passive"))
    )
    (net (code "40") (name "P3V3Ap") (class "Default")
      (node (ref "C57") (pin "2") (pinfunction "2_2") (pintype "passive"))
      (node (ref "L7") (pin "2") (pinfunction "2_2") (pintype "passive"))
    )
    (net (code "41") (name "P3V3p") (class "Default")
      (node (ref "C136") (pin "1") (pinfunction "1_1") (pintype "passive"))
      (node (ref "C66") (pin "2") (pinfunction "2_2") (pintype "passive"))
      (node (ref "C68") (pin "1") (pinfunction "1_1") (pintype "passive"))
      (node (ref "IC2") (pin "8") (pinfunction "V+_8") (pintype "input"))
      (node (ref "IC20") (pin "5") (pinfunction "VOUT_5") (pintype "power_in"))
      (node (ref "IC38") (pin "8") (pinfunction "V+_8") (pintype "input"))
      (node (ref "L7") (pin "1") (pinfunction "1_1") (pintype "passive"))
    )
    (net (code "42") (name "P5V0Ap") (class "Default")
      (node (ref "C135") (pin "1") (pinfunction "1_1") (pintype "passive"))
      (node (ref "C47") (pin "2") (pinfunction "2_2") (pintype "passive"))
      (node (ref "IC20") (pin "1") (pinfunction "VIN_1") (pintype "input"))
      (node (ref "IC20") (pin "3") (pinfunction "EN_3") (pintype "input"))
      (node (ref "L3") (pin "2") (pinfunction "2_2") (pintype "passive"))
    )
    (net (code "43") (name "P5V0p") (class "Default")
      (node (ref "C42") (pin "2") (pinfunction "2_2") (pintype "passive"))
      (node (ref "C45") (pin "2") (pinfunction "2_2") (pintype "passive"))
      (node (ref "L3") (pin "1") (pinfunction "1_1") (pintype "passive"))
      (node (ref "L4") (pin "2") (pinfunction "2_2") (pintype "passive"))
      (node (ref "R7") (pin "2") (pinfunction "2_2") (pintype "passive"))
    )
    (net (code "44") (name "P12V0") (class "Default")
      (node (ref "C4") (pin "2") (pinfunction "2_2") (pintype "passive"))
      (node (ref "L2") (pin "1") (pinfunction "1_1") (pintype "passive"))
    )
    (net (code "45") (name "P12V0c") (class "Default")
      (node (ref "C30") (pin "1") (pinfunction "1_1") (pintype "passive"))
      (node (ref "C31") (pin "1") (pinfunction "1_1") (pintype "passive"))
      (node (ref "J11") (pin "1") (pinfunction "1_1") (pintype "bidirectional"))
      (node (ref "L2") (pin "4") (pinfunction "4_4") (pintype "passive"))
      (node (ref "R185") (pin "2") (pinfunction "2_2") (pintype "passive"))
      (node (ref "T18") (pin "7") (pinfunction "D_7") (pintype "passive"))
      (node (ref "T18") (pin "8") (pinfunction "D_8") (pintype "passive"))
    )
    (net (code "46") (name "P12V0p") (class "Default")
      (node (ref "C25") (pin "2") (pinfunction "2_2") (pintype "passive"))
      (node (ref "C32") (pin "2") (pinfunction "2_2") (pintype "passive"))
      (node (ref "C34") (pin "1") (pinfunction "1_1") (pintype "passive"))
      (node (ref "C35") (pin "1") (pinfunction "1_1") (pintype "passive"))
      (node (ref "C48") (pin "2") (pinfunction "2_2") (pintype "passive"))
      (node (ref "D34") (pin "1") (pinfunction "C_1") (pintype "passive"))
      (node (ref "D35") (pin "1") (pinfunction "C_1") (pintype "passive"))
      (node (ref "IC22") (pin "3") (pinfunction "VIN_3") (pintype "input"))
      (node (ref "R195") (pin "2") (pinfunction "2_2") (pintype "passive"))
      (node (ref "R32") (pin "2") (pinfunction "2_2") (pintype "passive"))
    )
    (net (code "47") (name "unconnected-(IC2-Boost-Pad1)") (class "Default")
      (node (ref "IC2") (pin "1") (pinfunction "Boost_1") (pintype "passive"))
    )
    (net (code "48") (name "unconnected-(IC2-OSC-Pad7)") (class "Default")
      (node (ref "IC2") (pin "7") (pinfunction "OSC_7") (pintype "passive"))
    )
    (net (code "49") (name "unconnected-(IC3-PFC_STOP-Pad9)") (class "Default")
      (node (ref "IC3") (pin "9") (pinfunction "PFC_STOP_9") (pintype "output"))
    )
    (net (code "50") (name "unconnected-(IC3-n.c.-Pad13)") (class "Default")
      (node (ref "IC3") (pin "13") (pinfunction "n.c._13") (pintype "passive"))
    )
    (net (code "51") (name "unconnected-(IC20-NC-Pad4)") (class "Default")
      (node (ref "IC20") (pin "4") (pinfunction "NC_4") (pintype "passive"))
    )
    (net (code "52") (name "unconnected-(IC22-EN-Pad5)") (class "Default")
      (node (ref "IC22") (pin "5") (pinfunction "EN_5") (pintype "input+no_connect"))
    )
    (net (code "53") (name "unconnected-(IC38-Boost-Pad1)") (class "Default")
      (node (ref "IC38") (pin "1") (pinfunction "Boost_1") (pintype "passive"))
    )
    (net (code "54") (name "unconnected-(IC38-OSC-Pad7)") (class "Default")
      (node (ref "IC38") (pin "7") (pinfunction "OSC_7") (pintype "passive"))
    )
  )
)
